# HueMini.net
KiCad netlist of a schematic drawn in EAGLE
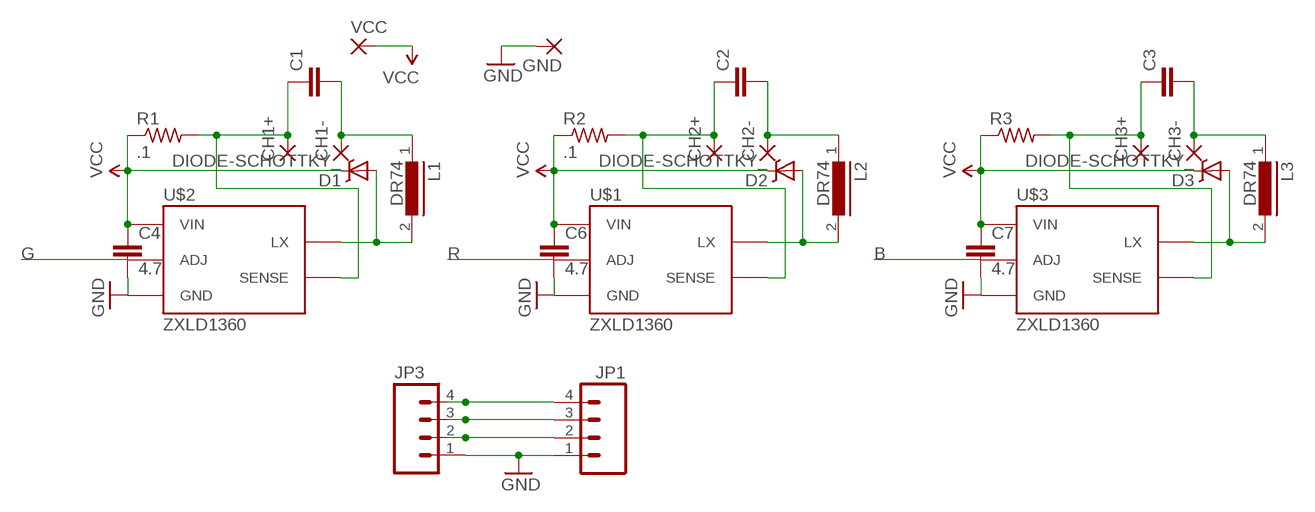
[diagram p0: schematic, sheet 1]

(export (version "E")
  (design (tool "Eeschema 10.0.6"))
  (components
    (comp (ref "C1")
      (value "CAP0603-CAP")
      (footprint "eagle-import:0603-CAP")
      (libsource (lib "eagle-import") (part "CAP0603-CAP"))
    )
    (comp (ref "C2")
      (value "CAP0603-CAP")
      (footprint "eagle-import:0603-CAP")
      (libsource (lib "eagle-import") (part "CAP0603-CAP"))
    )
    (comp (ref "C3")
      (value "CAP0603-CAP")
      (footprint "eagle-import:0603-CAP")
      (libsource (lib "eagle-import") (part "CAP0603-CAP"))
    )
    (comp (ref "C4")
      (value "4.7")
      (footprint "eagle-import:C1206")
      (libsource (lib "eagle-import") (part "C-EUC1206"))
    )
    (comp (ref "C6")
      (value "4.7")
      (footprint "eagle-import:C1206")
      (libsource (lib "eagle-import") (part "C-EUC1206"))
    )
    (comp (ref "C7")
      (value "4.7")
      (footprint "eagle-import:C1206")
      (libsource (lib "eagle-import") (part "C-EUC1206"))
    )
    (comp (ref "CH1+")
      (value "SMD5")
      (footprint "eagle-import:SMD2,54-5,08")
      (libsource (lib "eagle-import") (part "SMD5"))
    )
    (comp (ref "CH1-")
      (value "SMD5")
      (footprint "eagle-import:SMD2,54-5,08")
      (libsource (lib "eagle-import") (part "SMD5"))
    )
    (comp (ref "CH2+")
      (value "SMD5")
      (footprint "eagle-import:SMD2,54-5,08")
      (libsource (lib "eagle-import") (part "SMD5"))
    )
    (comp (ref "CH2-")
      (value "SMD5")
      (footprint "eagle-import:SMD2,54-5,08")
      (libsource (lib "eagle-import") (part "SMD5"))
    )
    (comp (ref "CH3+")
      (value "SMD5")
      (footprint "eagle-import:SMD2,54-5,08")
      (libsource (lib "eagle-import") (part "SMD5"))
    )
    (comp (ref "CH3-")
      (value "SMD5")
      (footprint "eagle-import:SMD2,54-5,08")
      (libsource (lib "eagle-import") (part "SMD5"))
    )
    (comp (ref "D1")
      (value "DIODE-SCHOTTKY_")
      (footprint "eagle-import:SMA-DIODE")
      (libsource (lib "eagle-import") (part "DIODE-SCHOTTKY_"))
    )
    (comp (ref "D2")
      (value "DIODE-SCHOTTKY_")
      (footprint "eagle-import:SMA-DIODE")
      (libsource (lib "eagle-import") (part "DIODE-SCHOTTKY_"))
    )
    (comp (ref "D3")
      (value "DIODE-SCHOTTKY_")
      (footprint "eagle-import:SMA-DIODE")
      (libsource (lib "eagle-import") (part "DIODE-SCHOTTKY_"))
    )
    (comp (ref "GND")
      (value "SMD5")
      (footprint "eagle-import:SMD2,54-5,08")
      (libsource (lib "eagle-import") (part "SMD5"))
    )
    (comp (ref "JP1")
      (value "M04PTH")
      (footprint "eagle-import:1X04")
      (libsource (lib "eagle-import") (part "M04PTH"))
    )
    (comp (ref "JP3")
      (value "M04PTH")
      (footprint "eagle-import:1X04")
      (libsource (lib "eagle-import") (part "M04PTH"))
    )
    (comp (ref "L1")
      (value "DR74")
      (footprint "eagle-import:DR74")
      (libsource (lib "eagle-import") (part "DR74"))
    )
    (comp (ref "L2")
      (value "DR74")
      (footprint "eagle-import:DR74")
      (libsource (lib "eagle-import") (part "DR74"))
    )
    (comp (ref "L3")
      (value "DR74")
      (footprint "eagle-import:DR74")
      (libsource (lib "eagle-import") (part "DR74"))
    )
    (comp (ref "R1")
      (value ".1")
      (footprint "eagle-import:R0603")
      (libsource (lib "eagle-import") (part "R-US_R0603"))
    )
    (comp (ref "R2")
      (value ".1")
      (footprint "eagle-import:R0603")
      (libsource (lib "eagle-import") (part "R-US_R0603"))
    )
    (comp (ref "R3")
      (value "R-US_R0603")
      (footprint "eagle-import:R0603")
      (libsource (lib "eagle-import") (part "R-US_R0603"))
    )
    (comp (ref "U$1")
      (value "ZXLD1360")
      (footprint "eagle-import:SOT23-5")
      (libsource (lib "eagle-import") (part "ZXLD1360"))
    )
    (comp (ref "U$2")
      (value "ZXLD1360")
      (footprint "eagle-import:SOT23-5")
      (libsource (lib "eagle-import") (part "ZXLD1360"))
    )
    (comp (ref "U$3")
      (value "ZXLD1360")
      (footprint "eagle-import:SOT23-5")
      (libsource (lib "eagle-import") (part "ZXLD1360"))
    )
    (comp (ref "VCC")
      (value "SMD5")
      (footprint "eagle-import:SMD2,54-5,08")
      (libsource (lib "eagle-import") (part "SMD5"))
    )
  )
  (nets
    (net (code "1") (name "/B") (class "Default")
      (node (ref "JP1") (pin "2") (pinfunction "2_2") (pintype "passive"))
      (node (ref "JP3") (pin "2") (pinfunction "2_2") (pintype "passive"))
      (node (ref "U$3") (pin "3") (pinfunction "ADJ_3") (pintype "bidirectional"))
    )
    (net (code "2") (name "/G") (class "Default")
      (node (ref "JP1") (pin "4") (pinfunction "4_4") (pintype "passive"))
      (node (ref "JP3") (pin "4") (pinfunction "4_4") (pintype "passive"))
      (node (ref "U$2") (pin "3") (pinfunction "ADJ_3") (pintype "bidirectional"))
    )
    (net (code "3") (name "/R") (class "Default")
      (node (ref "JP1") (pin "3") (pinfunction "3_3") (pintype "passive"))
      (node (ref "JP3") (pin "3") (pinfunction "3_3") (pintype "passive"))
      (node (ref "U$1") (pin "3") (pinfunction "ADJ_3") (pintype "bidirectional"))
    )
    (net (code "4") (name "GND") (class "Default")
      (node (ref "C4") (pin "2") (pinfunction "2_2") (pintype "passive"))
      (node (ref "C6") (pin "2") (pinfunction "2_2") (pintype "passive"))
      (node (ref "C7") (pin "2") (pinfunction "2_2") (pintype "passive"))
      (node (ref "GND") (pin "1") (pinfunction "P_1") (pintype "passive"))
      (node (ref "JP1") (pin "1") (pinfunction "1_1") (pintype "passive"))
      (node (ref "JP3") (pin "1") (pinfunction "1_1") (pintype "passive"))
      (node (ref "U$1") (pin "2") (pinfunction "GND_2") (pintype "bidirectional"))
      (node (ref "U$2") (pin "2") (pinfunction "GND_2") (pintype "bidirectional"))
      (node (ref "U$3") (pin "2") (pinfunction "GND_2") (pintype "bidirectional"))
    )
    (net (code "5") (name "Net-(CH1+-P)") (class "Default")
      (node (ref "C1") (pin "1") (pinfunction "1_1") (pintype "passive"))
      (node (ref "CH1+") (pin "1") (pinfunction "P_1") (pintype "passive"))
      (node (ref "R1") (pin "2") (pinfunction "2_2") (pintype "passive"))
      (node (ref "U$2") (pin "4") (pinfunction "SENSE_4") (pintype "bidirectional"))
    )
    (net (code "6") (name "Net-(CH1--P)") (class "Default")
      (node (ref "C1") (pin "2") (pinfunction "2_2") (pintype "passive"))
      (node (ref "CH1-") (pin "1") (pinfunction "P_1") (pintype "passive"))
      (node (ref "L1") (pin "1") (pinfunction "1_1") (pintype "passive"))
    )
    (net (code "7") (name "Net-(CH2+-P)") (class "Default")
      (node (ref "C2") (pin "1") (pinfunction "1_1") (pintype "passive"))
      (node (ref "CH2+") (pin "1") (pinfunction "P_1") (pintype "passive"))
      (node (ref "R2") (pin "2") (pinfunction "2_2") (pintype "passive"))
      (node (ref "U$1") (pin "4") (pinfunction "SENSE_4") (pintype "bidirectional"))
    )
    (net (code "8") (name "Net-(CH2--P)") (class "Default")
      (node (ref "C2") (pin "2") (pinfunction "2_2") (pintype "passive"))
      (node (ref "CH2-") (pin "1") (pinfunction "P_1") (pintype "passive"))
      (node (ref "L2") (pin "1") (pinfunction "1_1") (pintype "passive"))
    )
    (net (code "9") (name "Net-(CH3+-P)") (class "Default")
      (node (ref "C3") (pin "1") (pinfunction "1_1") (pintype "passive"))
      (node (ref "CH3+") (pin "1") (pinfunction "P_1") (pintype "passive"))
      (node (ref "R3") (pin "2") (pinfunction "2_2") (pintype "passive"))
      (node (ref "U$3") (pin "4") (pinfunction "SENSE_4") (pintype "bidirectional"))
    )
    (net (code "10") (name "Net-(CH3--P)") (class "Default")
      (node (ref "C3") (pin "2") (pinfunction "2_2") (pintype "passive"))
      (node (ref "CH3-") (pin "1") (pinfunction "P_1") (pintype "passive"))
      (node (ref "L3") (pin "1") (pinfunction "1_1") (pintype "passive"))
    )
    (net (code "11") (name "Net-(U$1-LX)") (class "Default")
      (node (ref "D2") (pin "A") (pinfunction "A_A") (pintype "passive"))
      (node (ref "L2") (pin "2") (pinfunction "2_2") (pintype "passive"))
      (node (ref "U$1") (pin "1") (pinfunction "LX_1") (pintype "bidirectional"))
    )
    (net (code "12") (name "Net-(U$2-LX)") (class "Default")
      (node (ref "D1") (pin "A") (pinfunction "A_A") (pintype "passive"))
      (node (ref "L1") (pin "2") (pinfunction "2_2") (pintype "passive"))
      (node (ref "U$2") (pin "1") (pinfunction "LX_1") (pintype "bidirectional"))
    )
    (net (code "13") (name "Net-(U$3-LX)") (class "Default")
      (node (ref "D3") (pin "A") (pinfunction "A_A") (pintype "passive"))
      (node (ref "L3") (pin "2") (pinfunction "2_2") (pintype "passive"))
      (node (ref "U$3") (pin "1") (pinfunction "LX_1") (pintype "bidirectional"))
    )
    (net (code "14") (name "VCC") (class "Default")
      (node (ref "C4") (pin "1") (pinfunction "1_1") (pintype "passive"))
      (node (ref "C6") (pin "1") (pinfunction "1_1") (pintype "passive"))
      (node (ref "C7") (pin "1") (pinfunction "1_1") (pintype "passive"))
      (node (ref "D1") (pin "C") (pinfunction "C_C") (pintype "passive"))
      (node (ref "D2") (pin "C") (pinfunction "C_C") (pintype "passive"))
      (node (ref "D3") (pin "C") (pinfunction "C_C") (pintype "passive"))
      (node (ref "R1") (pin "1") (pinfunction "1_1") (pintype "passive"))
      (node (ref "R2") (pin "1") (pinfunction "1_1") (pintype "passive"))
      (node (ref "R3") (pin "1") (pinfunction "1_1") (pintype "passive"))
      (node (ref "U$1") (pin "5") (pinfunction "VIN_5") (pintype "bidirectional"))
      (node (ref "U$2") (pin "5") (pinfunction "VIN_5") (pintype "bidirectional"))
      (node (ref "U$3") (pin "5") (pinfunction "VIN_5") (pintype "bidirectional"))
      (node (ref "VCC") (pin "1") (pinfunction "P_1") (pintype "passive"))
    )
  )
)
